# LB-word-PSU-24V.net
KiCad netlist of a schematic drawn in Altium Designer
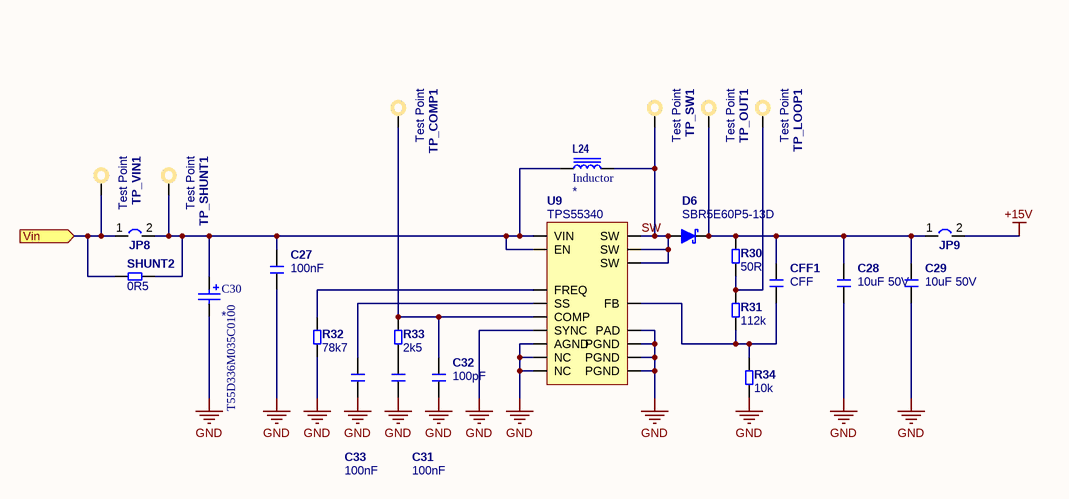
[diagram p0: LB-word-PSU-24V.SchDoc]

(export (version "E")
  (design (tool "Eeschema 10.0.6"))
  (components
    (comp (ref "C27")
      (value "100nF")
      (footprint "C0603_N")
      (description "Capacitor MLCC")
      (fields
        (field (name "MANUFACTURER") "Yageo")
        (field (name "MANUFACTURER PART NUMBER") "CC0603KRX7R9BB104")
      )
      (libsource (lib "wes") (part "Capacitor"))
    )
    (comp (ref "C28")
      (value "10uF 50V")
      (footprint "C1210_N")
      (description "Capacitor MLCC")
      (fields
        (field (name "MANUFACTURER") "Yageo")
        (field (name "MANUFACTURER PART NUMBER") "CC0603KRX7R9BB104")
      )
      (libsource (lib "wes") (part "Capacitor"))
    )
    (comp (ref "C29")
      (value "10uF 50V")
      (footprint "C1210_N")
      (description "Capacitor MLCC")
      (fields
        (field (name "MANUFACTURER") "Yageo")
        (field (name "MANUFACTURER PART NUMBER") "CC0603KRX7R9BB104")
      )
      (libsource (lib "wes") (part "Capacitor"))
    )
    (comp (ref "C30")
      (value "T55D336M035C0100")
      (footprint "2917 - Case D")
      (description "Polarized Cap")
      (fields (field (name "ALTIUM_VALUE") "*") (field (name "PUBLISHER") "Altium Limited"))
      (libsource (lib "wes") (part "Capacitor Polarized"))
    )
    (comp (ref "C31")
      (value "100nF")
      (footprint "C0603_N")
      (description "Capacitor MLCC")
      (fields
        (field (name "MANUFACTURER") "Yageo")
        (field (name "MANUFACTURER PART NUMBER") "CC0603KRX7R9BB104")
      )
      (libsource (lib "wes") (part "Capacitor"))
    )
    (comp (ref "C32")
      (value "100pF")
      (footprint "C0603_N")
      (description "Capacitor MLCC")
      (fields
        (field (name "MANUFACTURER") "Yageo")
        (field (name "MANUFACTURER PART NUMBER") "CC0603KRX7R9BB104")
      )
      (libsource (lib "wes") (part "Capacitor"))
    )
    (comp (ref "C33")
      (value "100nF")
      (footprint "C0603_N")
      (description "Capacitor MLCC")
      (fields
        (field (name "MANUFACTURER") "Yageo")
        (field (name "MANUFACTURER PART NUMBER") "CC0603KRX7R9BB104")
      )
      (libsource (lib "wes") (part "Capacitor"))
    )
    (comp (ref "CFF1")
      (value "CFF")
      (footprint "C0603_N")
      (description "Capacitor MLCC")
      (fields
        (field (name "MANUFACTURER") "Yageo")
        (field (name "MANUFACTURER PART NUMBER") "CC0603KRX7R9BB104")
      )
      (libsource (lib "wes") (part "Capacitor"))
    )
    (comp (ref "D6")
      (value "SBR5E60P5-13D")
      (footprint "PowerDI5")
      (libsource (lib "wes") (part "Diode Schottky"))
    )
    (comp (ref "JP8")
      (value "Jumper 2W")
      (footprint "Jumper SMD 2W NO")
      (libsource (lib "wes") (part "Jumper 2W"))
    )
    (comp (ref "JP9")
      (value "Jumper 2W")
      (footprint "Jumper SMD 2W NO")
      (libsource (lib "wes") (part "Jumper 2W"))
    )
    (comp (ref "L24")
      (value "Inductor")
      (footprint "INDUCTOR SRP1040")
      (fields (field (name "ALTIUM_VALUE") "*"))
      (libsource (lib "wes") (part "Inductor"))
    )
    (comp (ref "R30")
      (value "50R")
      (footprint "R0603")
      (fields (field (name "PUBLISHER") "Altium Limited"))
      (libsource (lib "wes") (part "Resistor"))
    )
    (comp (ref "R31")
      (value "112k")
      (footprint "R0603")
      (fields (field (name "PUBLISHER") "Altium Limited"))
      (libsource (lib "wes") (part "Resistor"))
    )
    (comp (ref "R32")
      (value "78k7")
      (footprint "R0603")
      (fields (field (name "PUBLISHER") "Altium Limited"))
      (libsource (lib "wes") (part "Resistor"))
    )
    (comp (ref "R33")
      (value "2k5")
      (footprint "R0603")
      (fields (field (name "PUBLISHER") "Altium Limited"))
      (libsource (lib "wes") (part "Resistor"))
    )
    (comp (ref "R34")
      (value "10k")
      (footprint "R0603")
      (fields (field (name "PUBLISHER") "Altium Limited"))
      (libsource (lib "wes") (part "Resistor"))
    )
    (comp (ref "SHUNT2")
      (value "0R5")
      (footprint "R0603")
      (fields (field (name "PUBLISHER") "Altium Limited"))
      (libsource (lib "wes") (part "Resistor"))
    )
    (comp (ref "TP_COMP1")
      (value "Test Point")
      (footprint "TestPoint-1.2mm")
      (libsource (lib "wes") (part "Test Point"))
    )
    (comp (ref "TP_LOOP1")
      (value "Test Point")
      (footprint "TestPoint-1.2mm")
      (libsource (lib "wes") (part "Test Point"))
    )
    (comp (ref "TP_OUT1")
      (value "Test Point")
      (footprint "TestPoint-1.2mm")
      (libsource (lib "wes") (part "Test Point"))
    )
    (comp (ref "TP_SHUNT1")
      (value "Test Point")
      (footprint "TestPoint-1.2mm")
      (libsource (lib "wes") (part "Test Point"))
    )
    (comp (ref "TP_SW1")
      (value "Test Point")
      (footprint "TestPoint-1.2mm")
      (libsource (lib "wes") (part "Test Point"))
    )
    (comp (ref "TP_VIN1")
      (value "Test Point")
      (footprint "TestPoint-1.2mm")
      (libsource (lib "wes") (part "Test Point"))
    )
    (comp (ref "U9")
      (value "TPS55340")
      (footprint "QFN16")
      (description "Boost/SEPIC/Flyback converter")
      (libsource (lib "wes") (part "TPS55340"))
    )
  )
  (nets
    (net (code "1") (name "+15V") (class "Default")
      (node (ref "JP9") (pin "2") (pinfunction "2_2") (pintype "passive"))
    )
    (net (code "2") (name "/SW") (class "Default")
      (node (ref "D6") (pin "A") (pinfunction "A_A") (pintype "passive"))
      (node (ref "L24") (pin "2") (pinfunction "2_2") (pintype "passive"))
      (node (ref "TP_SW1") (pin "1") (pinfunction "1_1") (pintype "passive"))
      (node (ref "U9") (pin "1") (pinfunction "SW_1") (pintype "passive"))
      (node (ref "U9") (pin "15") (pinfunction "SW_15") (pintype "passive"))
      (node (ref "U9") (pin "16") (pinfunction "SW_16") (pintype "passive"))
    )
    (net (code "3") (name "/Vin") (class "Default")
      (node (ref "JP8") (pin "1") (pinfunction "1_1") (pintype "passive"))
      (node (ref "SHUNT2") (pin "1") (pinfunction "1_1") (pintype "passive"))
      (node (ref "TP_VIN1") (pin "1") (pinfunction "1_1") (pintype "passive"))
    )
    (net (code "4") (name "GND") (class "Default")
      (node (ref "C27") (pin "2") (pintype "passive"))
      (node (ref "C28") (pin "2") (pintype "passive"))
      (node (ref "C29") (pin "2") (pintype "passive"))
      (node (ref "C30") (pin "2") (pinfunction "2_2") (pintype "passive"))
      (node (ref "C31") (pin "2") (pintype "passive"))
      (node (ref "C32") (pin "2") (pintype "passive"))
      (node (ref "C33") (pin "2") (pintype "passive"))
      (node (ref "R32") (pin "1") (pinfunction "1_1") (pintype "passive"))
      (node (ref "R34") (pin "1") (pinfunction "1_1") (pintype "passive"))
      (node (ref "U9") (pin "10") (pinfunction "NC_10") (pintype "passive"))
      (node (ref "U9") (pin "11") (pinfunction "PGND_11") (pintype "passive"))
      (node (ref "U9") (pin "12") (pinfunction "PGND_12") (pintype "passive"))
      (node (ref "U9") (pin "13") (pinfunction "PGND_13") (pintype "passive"))
      (node (ref "U9") (pin "14") (pinfunction "NC_14") (pintype "passive"))
      (node (ref "U9") (pin "5") (pinfunction "SYNC_5") (pintype "passive"))
      (node (ref "U9") (pin "6") (pinfunction "AGND_6") (pintype "passive"))
      (node (ref "U9") (pin "PAD") (pinfunction "PAD_PAD") (pintype "passive"))
    )
    (net (code "5") (name "Net-(C28-Pad1)") (class "Default")
      (node (ref "C28") (pin "1") (pintype "passive"))
      (node (ref "C29") (pin "1") (pintype "passive"))
      (node (ref "CFF1") (pin "1") (pintype "passive"))
      (node (ref "D6") (pin "K") (pinfunction "K_K") (pintype "passive"))
      (node (ref "JP9") (pin "1") (pinfunction "1_1") (pintype "passive"))
      (node (ref "R30") (pin "2") (pinfunction "2_2") (pintype "passive"))
      (node (ref "TP_OUT1") (pin "1") (pinfunction "1_1") (pintype "passive"))
    )
    (net (code "6") (name "Net-(C31-Pad1)") (class "Default")
      (node (ref "C31") (pin "1") (pintype "passive"))
      (node (ref "R33") (pin "1") (pinfunction "1_1") (pintype "passive"))
    )
    (net (code "7") (name "Net-(R30-Pad1)") (class "Default")
      (node (ref "R30") (pin "1") (pinfunction "1_1") (pintype "passive"))
      (node (ref "R31") (pin "2") (pinfunction "2_2") (pintype "passive"))
      (node (ref "TP_LOOP1") (pin "1") (pinfunction "1_1") (pintype "passive"))
    )
    (net (code "8") (name "Net-(U9-COMP)") (class "Default")
      (node (ref "C32") (pin "1") (pintype "passive"))
      (node (ref "R33") (pin "2") (pinfunction "2_2") (pintype "passive"))
      (node (ref "TP_COMP1") (pin "1") (pinfunction "1_1") (pintype "passive"))
      (node (ref "U9") (pin "7") (pinfunction "COMP_7") (pintype "passive"))
    )
    (net (code "9") (name "Net-(U9-EN)") (class "Default")
      (node (ref "C27") (pin "1") (pintype "passive"))
      (node (ref "C30") (pin "1") (pinfunction "1_1") (pintype "passive"))
      (node (ref "JP8") (pin "2") (pinfunction "2_2") (pintype "passive"))
      (node (ref "L24") (pin "1") (pinfunction "1_1") (pintype "passive"))
      (node (ref "SHUNT2") (pin "2") (pinfunction "2_2") (pintype "passive"))
      (node (ref "TP_SHUNT1") (pin "1") (pinfunction "1_1") (pintype "passive"))
      (node (ref "U9") (pin "2") (pinfunction "VIN_2") (pintype "passive"))
      (node (ref "U9") (pin "3") (pinfunction "EN_3") (pintype "passive"))
    )
    (net (code "10") (name "Net-(U9-FB)") (class "Default")
      (node (ref "CFF1") (pin "2") (pintype "passive"))
      (node (ref "R31") (pin "1") (pinfunction "1_1") (pintype "passive"))
      (node (ref "R34") (pin "2") (pinfunction "2_2") (pintype "passive"))
      (node (ref "U9") (pin "8") (pinfunction "FB_8") (pintype "passive"))
    )
    (net (code "11") (name "Net-(U9-FREQ)") (class "Default")
      (node (ref "R32") (pin "2") (pinfunction "2_2") (pintype "passive"))
      (node (ref "U9") (pin "9") (pinfunction "FREQ_9") (pintype "passive"))
    )
    (net (code "12") (name "Net-(U9-SS)") (class "Default")
      (node (ref "C33") (pin "1") (pintype "passive"))
      (node (ref "U9") (pin "4") (pinfunction "SS_4") (pintype "passive"))
    )
  )
)
